# Triangulator-LM358.net
KiCad netlist of a schematic drawn in EAGLE
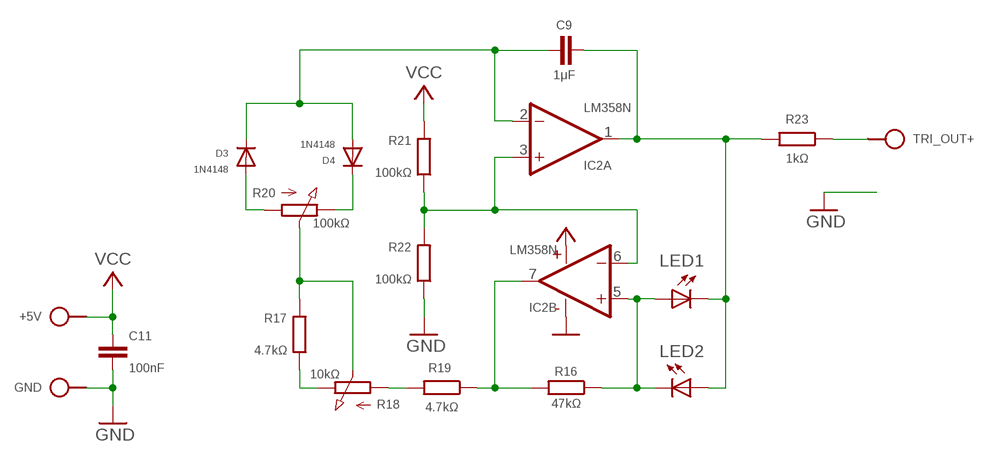
[diagram p0: schematic, sheet 1]

(export (version "E")
  (design (tool "Eeschema 10.0.6"))
  (components
    (comp (ref "+5V")
      (value "VCC")
      (footprint "eagle-import:SPAD")
      (libsource (lib "eagle-import") (part "SPAD"))
    )
    (comp (ref "C9")
      (value "1μF")
      (footprint "eagle-import:C050-020X036_V")
      (libsource (lib "eagle-import") (part "C050-020X036/V"))
    )
    (comp (ref "C11")
      (value "100nF")
      (footprint "eagle-import:C050-020X036")
      (libsource (lib "eagle-import") (part "C050-020X036"))
    )
    (comp (ref "D3")
      (value "1N4148")
      (footprint "eagle-import:DO34-5V")
      (libsource (lib "eagle-import") (part "1N414834-5V"))
    )
    (comp (ref "D4")
      (value "1N4148")
      (footprint "eagle-import:DO34-5V")
      (libsource (lib "eagle-import") (part "1N414834-5V"))
    )
    (comp (ref "GND")
      (value "GND")
      (footprint "eagle-import:SPAD")
      (libsource (lib "eagle-import") (part "SPAD"))
    )
    (comp (ref "IC2")
      (value "LM358N")
      (footprint "eagle-import:DIL08")
      (libsource (lib "eagle-import") (part "LM358N"))
    )
    (comp (ref "LED1")
      (value "LED3MM")
      (footprint "eagle-import:LED3MM")
      (libsource (lib "eagle-import") (part "LED3MM"))
    )
    (comp (ref "LED2")
      (value "LED3MM")
      (footprint "eagle-import:LED3MM")
      (libsource (lib "eagle-import") (part "LED3MM"))
    )
    (comp (ref "R16")
      (value "47kΩ")
      (footprint "eagle-import:0202_7-V")
      (libsource (lib "eagle-import") (part "R0202/7-V"))
    )
    (comp (ref "R17")
      (value "4.7kΩ")
      (footprint "eagle-import:0202_7")
      (libsource (lib "eagle-import") (part "R0202/7"))
    )
    (comp (ref "R18")
      (value "10kΩ")
      (footprint "eagle-import:POT")
      (libsource (lib "eagle-import") (part "POT"))
    )
    (comp (ref "R19")
      (value "4.7kΩ")
      (footprint "eagle-import:0202_7-V")
      (libsource (lib "eagle-import") (part "R0202/7-V"))
    )
    (comp (ref "R20")
      (value "100kΩ")
      (footprint "eagle-import:POT")
      (libsource (lib "eagle-import") (part "POT"))
    )
    (comp (ref "R21")
      (value "100kΩ")
      (footprint "eagle-import:0202_7-V")
      (libsource (lib "eagle-import") (part "R0202/7-V"))
    )
    (comp (ref "R22")
      (value "100kΩ")
      (footprint "eagle-import:0202_7-V")
      (libsource (lib "eagle-import") (part "R0202/7-V"))
    )
    (comp (ref "R23")
      (value "1kΩ")
      (footprint "eagle-import:0202_5")
      (libsource (lib "eagle-import") (part "R0202/5"))
    )
    (comp (ref "TRI_OUT+")
      (value "TRIANGLE")
      (footprint "eagle-import:SPAD")
      (libsource (lib "eagle-import") (part "SPAD"))
    )
  )
  (nets
    (net (code "1") (name "GND") (class "Default")
      (node (ref "C11") (pin "2") (pinfunction "2_2") (pintype "passive"))
      (node (ref "GND") (pin "1") (pinfunction "P$1_1") (pintype "bidirectional"))
      (node (ref "IC2") (pin "4") (pinfunction "V-_4") (pintype "power_in"))
      (node (ref "R22") (pin "1") (pinfunction "1_1") (pintype "passive"))
    )
    (net (code "2") (name "Net-(IC2A-+IN)") (class "Default")
      (node (ref "IC2") (pin "3") (pinfunction "+IN_3") (pintype "input"))
      (node (ref "IC2") (pin "6") (pinfunction "-IN_6") (pintype "input"))
      (node (ref "R21") (pin "1") (pinfunction "1_1") (pintype "passive"))
      (node (ref "R22") (pin "2") (pinfunction "2_2") (pintype "passive"))
    )
    (net (code "3") (name "Net-(IC2A--IN)") (class "Default")
      (node (ref "C9") (pin "1") (pinfunction "1_1") (pintype "passive"))
      (node (ref "D3") (pin "C") (pinfunction "C_C") (pintype "passive"))
      (node (ref "D4") (pin "A") (pinfunction "A_A") (pintype "passive"))
      (node (ref "IC2") (pin "2") (pinfunction "-IN_2") (pintype "input"))
    )
    (net (code "4") (name "Net-(IC2A-OUT)") (class "Default")
      (node (ref "C9") (pin "2") (pinfunction "2_2") (pintype "passive"))
      (node (ref "IC2") (pin "1") (pinfunction "OUT_1") (pintype "output"))
      (node (ref "LED1") (pin "K") (pinfunction "C_K") (pintype "passive"))
      (node (ref "LED2") (pin "A") (pinfunction "A_A") (pintype "passive"))
      (node (ref "R23") (pin "2") (pinfunction "2_2") (pintype "passive"))
    )
    (net (code "5") (name "Net-(IC2B-+IN)") (class "Default")
      (node (ref "IC2") (pin "5") (pinfunction "+IN_5") (pintype "input"))
      (node (ref "LED1") (pin "A") (pinfunction "A_A") (pintype "passive"))
      (node (ref "LED2") (pin "K") (pinfunction "C_K") (pintype "passive"))
      (node (ref "R16") (pin "1") (pinfunction "1_1") (pintype "passive"))
    )
    (net (code "6") (name "Net-(IC2B-OUT)") (class "Default")
      (node (ref "IC2") (pin "7") (pinfunction "OUT_7") (pintype "output"))
      (node (ref "R16") (pin "2") (pinfunction "2_2") (pintype "passive"))
      (node (ref "R19") (pin "1") (pinfunction "1_1") (pintype "passive"))
    )
    (net (code "7") (name "Net-(R18-A)") (class "Default")
      (node (ref "R18") (pin "1") (pinfunction "A_1") (pintype "passive"))
      (node (ref "R19") (pin "2") (pinfunction "2_2") (pintype "passive"))
    )
    (net (code "8") (name "Net-(R18-E)") (class "Default")
      (node (ref "R17") (pin "1") (pinfunction "1_1") (pintype "passive"))
      (node (ref "R18") (pin "3") (pinfunction "E_3") (pintype "passive"))
    )
    (net (code "9") (name "Net-(R18-S)") (class "Default")
      (node (ref "R17") (pin "2") (pinfunction "2_2") (pintype "passive"))
      (node (ref "R18") (pin "2") (pinfunction "S_2") (pintype "passive"))
      (node (ref "R20") (pin "2") (pinfunction "S_2") (pintype "passive"))
    )
    (net (code "10") (name "Net-(R20-A)") (class "Default")
      (node (ref "D3") (pin "A") (pinfunction "A_A") (pintype "passive"))
      (node (ref "R20") (pin "1") (pinfunction "A_1") (pintype "passive"))
    )
    (net (code "11") (name "Net-(R20-E)") (class "Default")
      (node (ref "D4") (pin "C") (pinfunction "C_C") (pintype "passive"))
      (node (ref "R20") (pin "3") (pinfunction "E_3") (pintype "passive"))
    )
    (net (code "12") (name "Net-(TRI_OUT+-P$1)") (class "Default")
      (node (ref "R23") (pin "1") (pinfunction "1_1") (pintype "passive"))
      (node (ref "TRI_OUT+") (pin "1") (pinfunction "P$1_1") (pintype "bidirectional"))
    )
    (net (code "13") (name "VCC") (class "Default")
      (node (ref "+5V") (pin "1") (pinfunction "P$1_1") (pintype "bidirectional"))
      (node (ref "C11") (pin "1") (pinfunction "1_1") (pintype "passive"))
      (node (ref "IC2") (pin "8") (pinfunction "V+_8") (pintype "power_in"))
      (node (ref "R21") (pin "2") (pinfunction "2_2") (pintype "passive"))
    )
  )
)
